# Crystal_Cmoy_Sch_EaglePCB_1.net
KiCad netlist of a schematic drawn in EAGLE
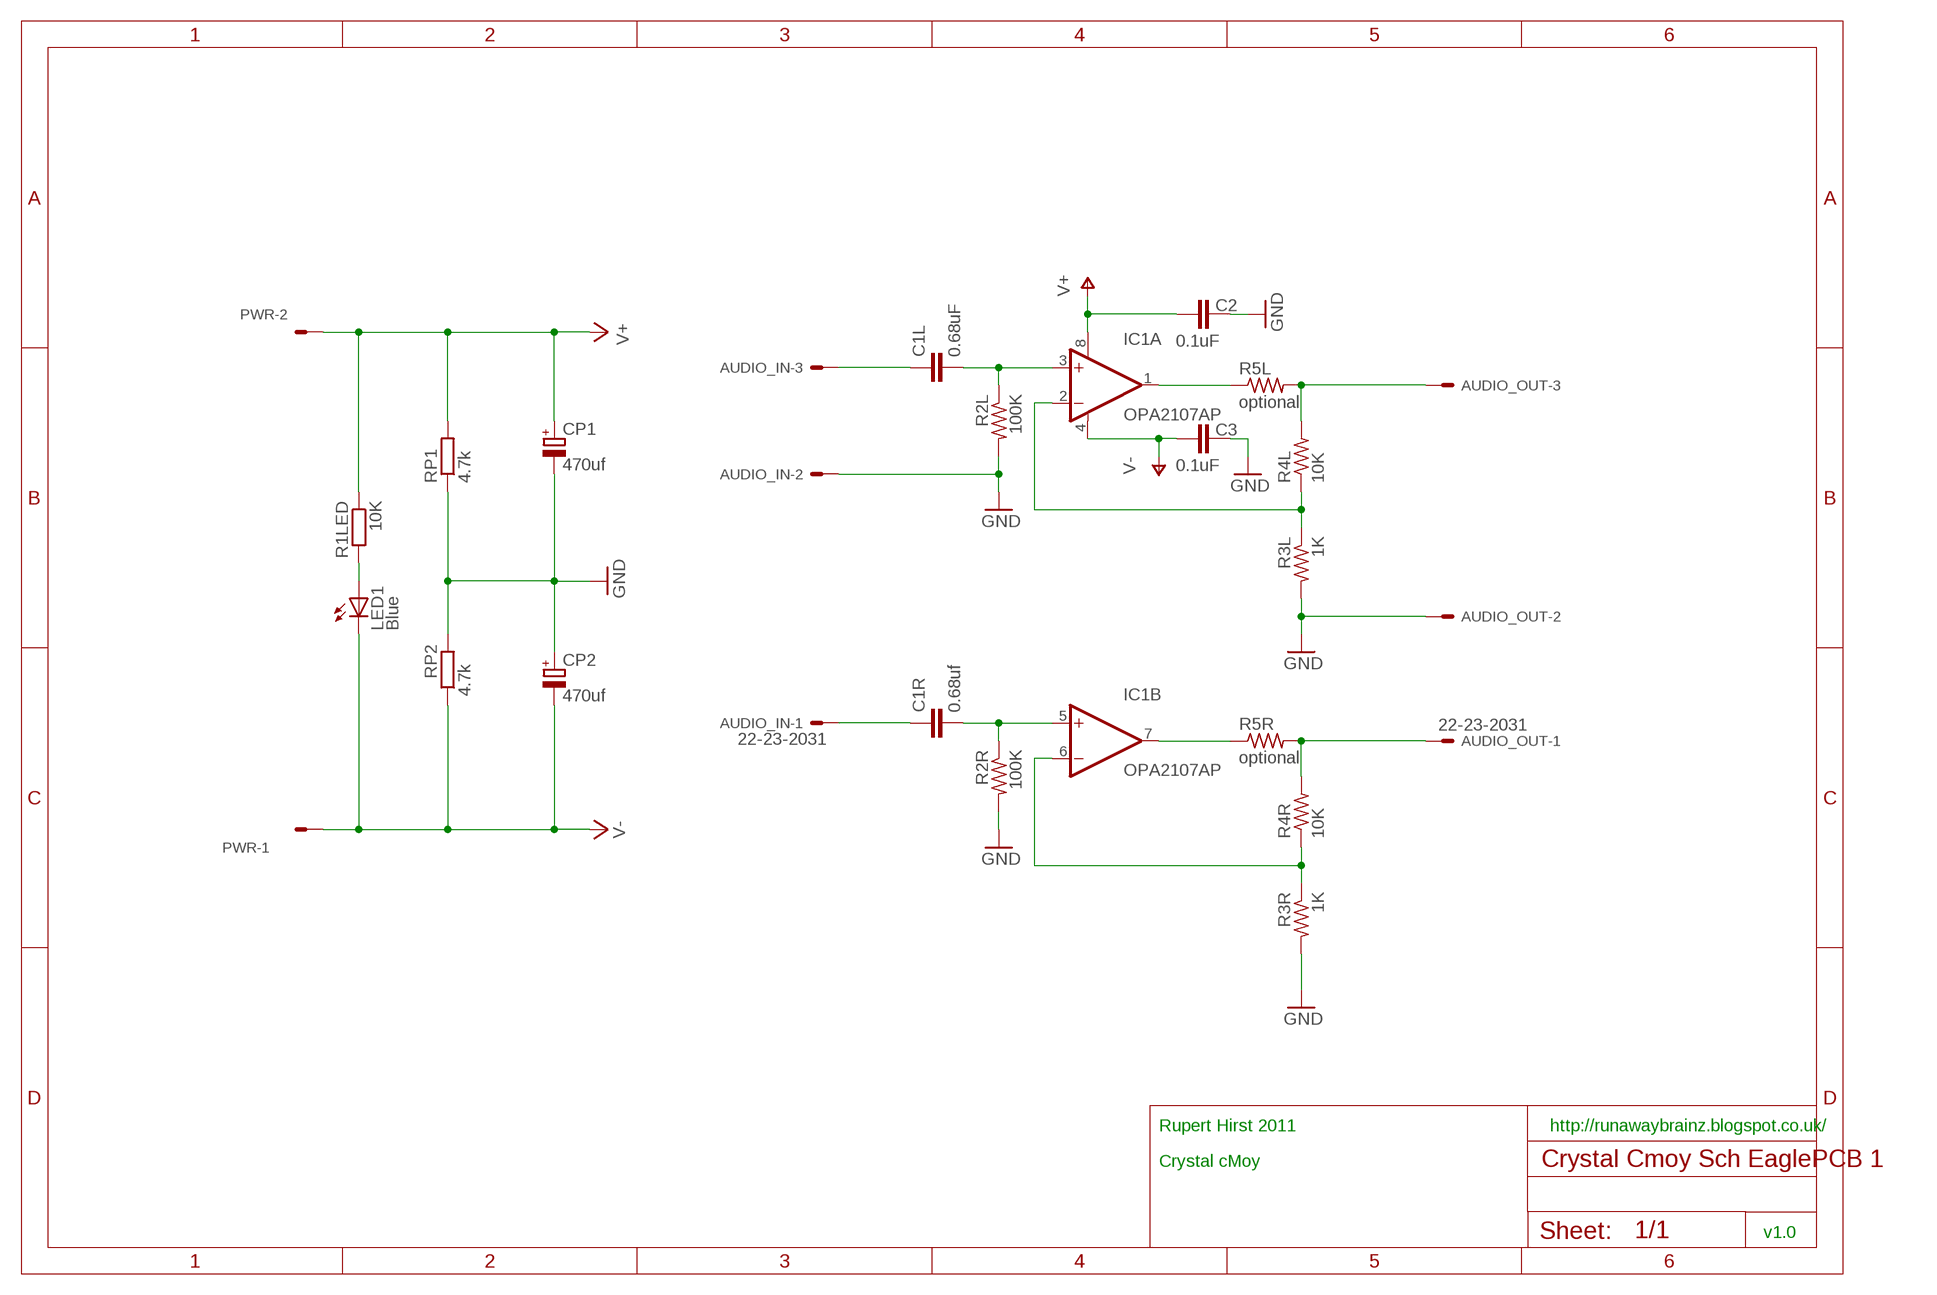
[diagram p0: schematic, sheet 1]

(export (version "E")
  (design (tool "Eeschema 10.0.6"))
  (components
    (comp (ref "AUDIO_IN")
      (value "22-23-2031")
      (footprint "eagle-import:22-23-2031")
      (libsource (lib "eagle-import") (part "22-23-2031"))
    )
    (comp (ref "AUDIO_OUT")
      (value "22-23-2031")
      (footprint "eagle-import:22-23-2031")
      (libsource (lib "eagle-import") (part "22-23-2031"))
    )
    (comp (ref "C1L")
      (value "0.68uF")
      (footprint "eagle-import:C15B7")
      (libsource (lib "eagle-import") (part "C15/7"))
    )
    (comp (ref "C1R")
      (value "0.68uf")
      (footprint "eagle-import:C15B7")
      (libsource (lib "eagle-import") (part "C15/7"))
    )
    (comp (ref "C2")
      (value "0.1uF")
      (footprint "eagle-import:C5B2.5")
      (libsource (lib "eagle-import") (part "C5/2.5"))
    )
    (comp (ref "C3")
      (value "0.1uF")
      (footprint "eagle-import:C5B5.5")
      (libsource (lib "eagle-import") (part "C5/5.5"))
    )
    (comp (ref "CP1")
      (value "470uf")
      (footprint "eagle-import:E5-13")
      (libsource (lib "eagle-import") (part "CPOL-EUE5-13"))
    )
    (comp (ref "CP2")
      (value "470uf")
      (footprint "eagle-import:E5-13")
      (libsource (lib "eagle-import") (part "CPOL-EUE5-13"))
    )
    (comp (ref "IC1")
      (value "OPA2107AP")
      (footprint "eagle-import:DIL08")
      (libsource (lib "eagle-import") (part "OPA2132P"))
    )
    (comp (ref "LED1")
      (value "Blue")
      (footprint "eagle-import:LED3MM")
      (libsource (lib "eagle-import") (part "LED3MM"))
    )
    (comp (ref "PWR")
      (value "22-23-2021")
      (footprint "eagle-import:22-23-2021")
      (libsource (lib "eagle-import") (part "22-23-2021"))
    )
    (comp (ref "R1LED")
      (value "10K")
      (footprint "eagle-import:0207_2V")
      (libsource (lib "eagle-import") (part "R-EU_0207/2V"))
    )
    (comp (ref "R2L")
      (value "100K")
      (footprint "eagle-import:0207_10")
      (libsource (lib "eagle-import") (part "R-US_0207/10"))
    )
    (comp (ref "R2R")
      (value "100K")
      (footprint "eagle-import:0207_10")
      (libsource (lib "eagle-import") (part "R-US_0207/10"))
    )
    (comp (ref "R3L")
      (value "1K")
      (footprint "eagle-import:0207_10")
      (libsource (lib "eagle-import") (part "R-US_0207/10"))
    )
    (comp (ref "R3R")
      (value "1K")
      (footprint "eagle-import:0207_10")
      (libsource (lib "eagle-import") (part "R-US_0207/10"))
    )
    (comp (ref "R4L")
      (value "10K")
      (footprint "eagle-import:0207_10")
      (libsource (lib "eagle-import") (part "R-US_0207/10"))
    )
    (comp (ref "R4R")
      (value "10K")
      (footprint "eagle-import:0207_10")
      (libsource (lib "eagle-import") (part "R-US_0207/10"))
    )
    (comp (ref "R5L")
      (value "optional")
      (footprint "eagle-import:0207_10")
      (libsource (lib "eagle-import") (part "R-US_0207/10"))
    )
    (comp (ref "R5R")
      (value "optional")
      (footprint "eagle-import:0207_10")
      (libsource (lib "eagle-import") (part "R-US_0207/10"))
    )
    (comp (ref "RP1")
      (value "4.7k")
      (footprint "eagle-import:0207_10")
      (libsource (lib "eagle-import") (part "R-EU_0207/10"))
    )
    (comp (ref "RP2")
      (value "4.7k")
      (footprint "eagle-import:0207_10")
      (libsource (lib "eagle-import") (part "R-EU_0207/10"))
    )
  )
  (nets
    (net (code "1") (name "GND") (class "Default")
      (node (ref "AUDIO_IN") (pin "2") (pinfunction "S_2") (pintype "passive"))
      (node (ref "AUDIO_OUT") (pin "2") (pinfunction "S_2") (pintype "passive"))
      (node (ref "C2") (pin "1") (pinfunction "1_1") (pintype "passive"))
      (node (ref "C3") (pin "2") (pinfunction "2_2") (pintype "passive"))
      (node (ref "CP1") (pin "-") (pinfunction "-_-") (pintype "passive"))
      (node (ref "CP2") (pin "+") (pinfunction "+_+") (pintype "passive"))
      (node (ref "R2L") (pin "2") (pinfunction "2_2") (pintype "passive"))
      (node (ref "R2R") (pin "2") (pinfunction "2_2") (pintype "passive"))
      (node (ref "R3L") (pin "2") (pinfunction "2_2") (pintype "passive"))
      (node (ref "R3R") (pin "2") (pinfunction "2_2") (pintype "passive"))
      (node (ref "RP1") (pin "1") (pinfunction "1_1") (pintype "passive"))
      (node (ref "RP2") (pin "2") (pinfunction "2_2") (pintype "passive"))
    )
    (net (code "2") (name "Net-(AUDIO_INA-S)") (class "Default")
      (node (ref "AUDIO_IN") (pin "1") (pinfunction "S_1") (pintype "passive"))
      (node (ref "C1R") (pin "1") (pinfunction "1_1") (pintype "passive"))
    )
    (net (code "3") (name "Net-(AUDIO_INC-S)") (class "Default")
      (node (ref "AUDIO_IN") (pin "3") (pinfunction "S_3") (pintype "passive"))
      (node (ref "C1L") (pin "1") (pinfunction "1_1") (pintype "passive"))
    )
    (net (code "4") (name "Net-(AUDIO_OUTA-S)") (class "Default")
      (node (ref "AUDIO_OUT") (pin "1") (pinfunction "S_1") (pintype "passive"))
      (node (ref "R4R") (pin "2") (pinfunction "2_2") (pintype "passive"))
      (node (ref "R5R") (pin "2") (pinfunction "2_2") (pintype "passive"))
    )
    (net (code "5") (name "Net-(AUDIO_OUTC-S)") (class "Default")
      (node (ref "AUDIO_OUT") (pin "3") (pinfunction "S_3") (pintype "passive"))
      (node (ref "R4L") (pin "2") (pinfunction "2_2") (pintype "passive"))
      (node (ref "R5L") (pin "2") (pinfunction "2_2") (pintype "passive"))
    )
    (net (code "6") (name "Net-(IC1A-+IN)") (class "Default")
      (node (ref "C1L") (pin "2") (pinfunction "2_2") (pintype "passive"))
      (node (ref "IC1") (pin "3") (pinfunction "+IN_3") (pintype "input"))
      (node (ref "R2L") (pin "1") (pinfunction "1_1") (pintype "passive"))
    )
    (net (code "7") (name "Net-(IC1A--IN)") (class "Default")
      (node (ref "IC1") (pin "2") (pinfunction "-IN_2") (pintype "input"))
      (node (ref "R3L") (pin "1") (pinfunction "1_1") (pintype "passive"))
      (node (ref "R4L") (pin "1") (pinfunction "1_1") (pintype "passive"))
    )
    (net (code "8") (name "Net-(IC1A-OUT)") (class "Default")
      (node (ref "IC1") (pin "1") (pinfunction "OUT_1") (pintype "output"))
      (node (ref "R5L") (pin "1") (pinfunction "1_1") (pintype "passive"))
    )
    (net (code "9") (name "Net-(IC1B-+IN)") (class "Default")
      (node (ref "C1R") (pin "2") (pinfunction "2_2") (pintype "passive"))
      (node (ref "IC1") (pin "5") (pinfunction "+IN_5") (pintype "input"))
      (node (ref "R2R") (pin "1") (pinfunction "1_1") (pintype "passive"))
    )
    (net (code "10") (name "Net-(IC1B--IN)") (class "Default")
      (node (ref "IC1") (pin "6") (pinfunction "-IN_6") (pintype "input"))
      (node (ref "R3R") (pin "1") (pinfunction "1_1") (pintype "passive"))
      (node (ref "R4R") (pin "1") (pinfunction "1_1") (pintype "passive"))
    )
    (net (code "11") (name "Net-(IC1B-OUT)") (class "Default")
      (node (ref "IC1") (pin "7") (pinfunction "OUT_7") (pintype "output"))
      (node (ref "R5R") (pin "1") (pinfunction "1_1") (pintype "passive"))
    )
    (net (code "12") (name "Net-(LED1-PadA)") (class "Default")
      (node (ref "LED1") (pin "A") (pinfunction "A_A") (pintype "passive"))
      (node (ref "R1LED") (pin "2") (pinfunction "2_2") (pintype "passive"))
    )
    (net (code "13") (name "V+") (class "Default")
      (node (ref "C2") (pin "2") (pinfunction "2_2") (pintype "passive"))
      (node (ref "CP1") (pin "+") (pinfunction "+_+") (pintype "passive"))
      (node (ref "IC1") (pin "8") (pinfunction "V+_8") (pintype "power_in"))
      (node (ref "PWR") (pin "2") (pinfunction "S_2") (pintype "passive"))
      (node (ref "R1LED") (pin "1") (pinfunction "1_1") (pintype "passive"))
      (node (ref "RP1") (pin "2") (pinfunction "2_2") (pintype "passive"))
    )
    (net (code "14") (name "V-") (class "Default")
      (node (ref "C3") (pin "1") (pinfunction "1_1") (pintype "passive"))
      (node (ref "CP2") (pin "-") (pinfunction "-_-") (pintype "passive"))
      (node (ref "IC1") (pin "4") (pinfunction "V-_4") (pintype "power_in"))
      (node (ref "LED1") (pin "K") (pinfunction "C_K") (pintype "passive"))
      (node (ref "PWR") (pin "1") (pinfunction "S_1") (pintype "passive"))
      (node (ref "RP2") (pin "1") (pinfunction "1_1") (pintype "passive"))
    )
  )
)
